# 02cpu_power.net
KiCad netlist of a schematic drawn in Altium Designer
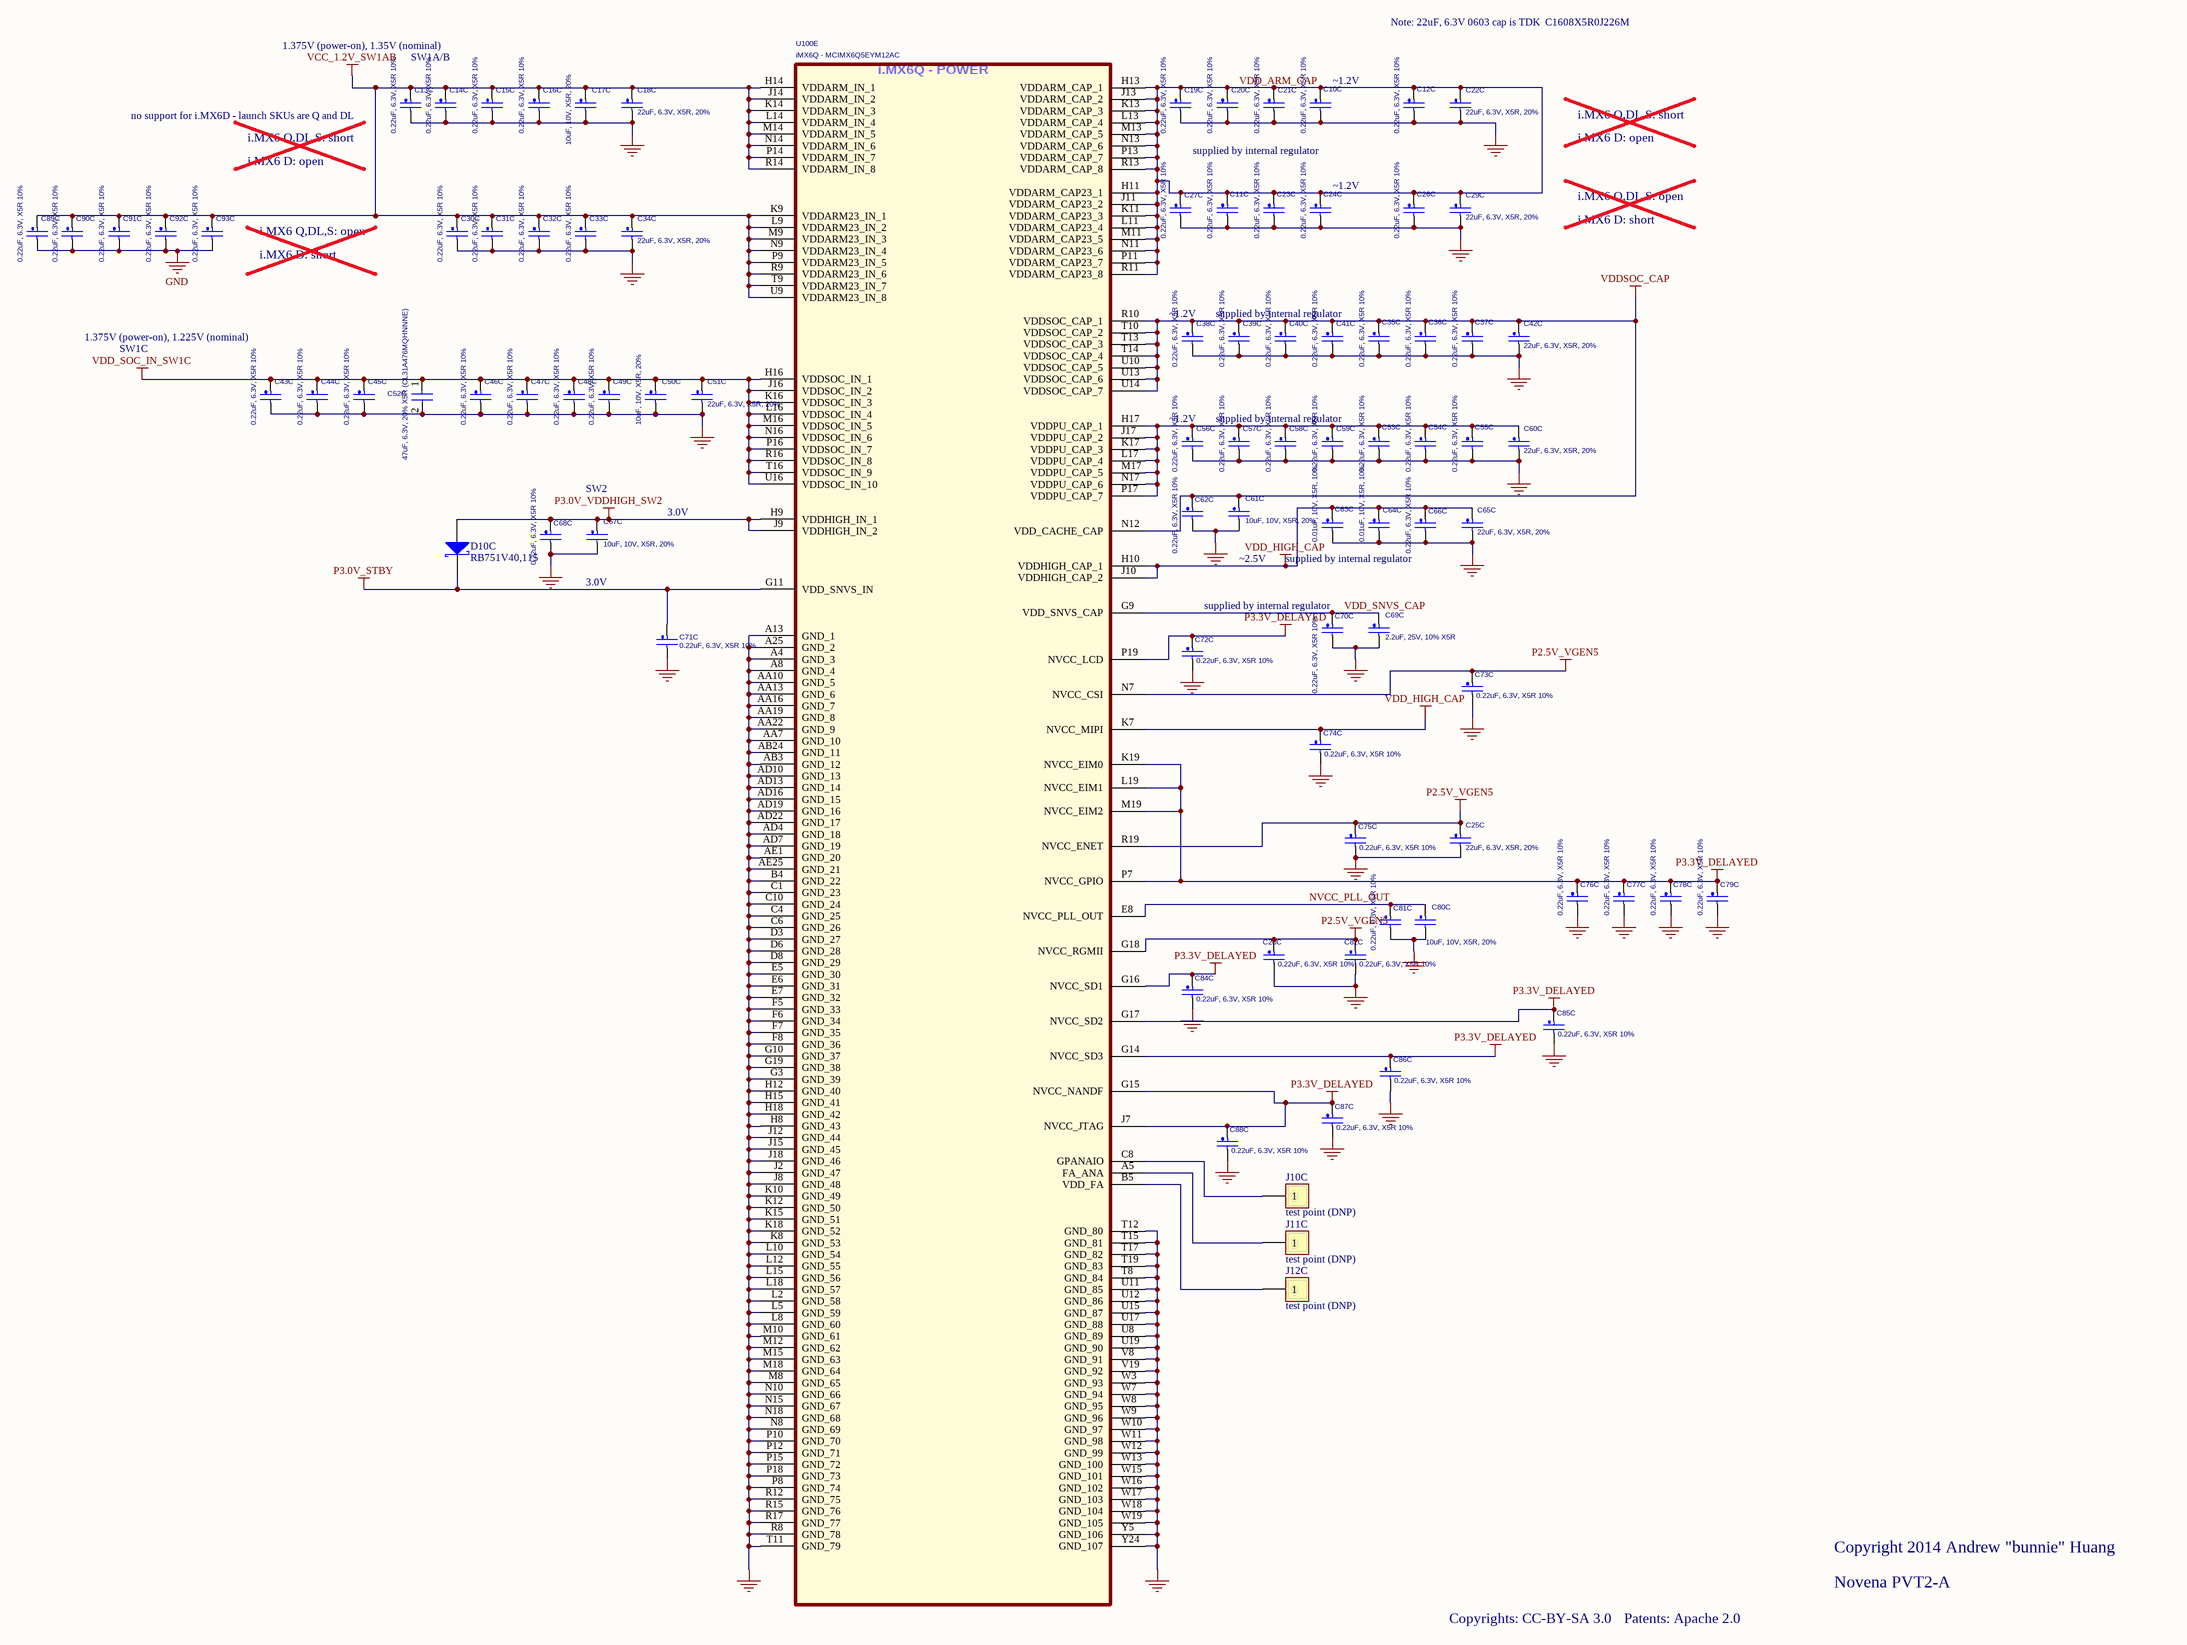
[diagram p0: 02cpu_power.SchDoc]

(export (version "E")
  (design (tool "Eeschema 10.0.6"))
  (components
    (comp (ref "C10C")
      (value "0.22uF, 6.3V, X5R 10%")
      (footprint "CAPC0603N_B")
      (description "CAP CER 0.22UF 6.3V 20% X5R 0201")
      (fields (field (name "TOLERANCE") "10%"))
      (libsource (lib "*") (part "CAP_NP_Dup1"))
    )
    (comp (ref "C11C")
      (value "0.22uF, 6.3V, X5R 10%")
      (footprint "CAPC0603N_B")
      (description "CAP CER 0.22UF 6.3V 20% X5R 0201")
      (fields (field (name "TOLERANCE") "10%"))
      (libsource (lib "*") (part "CAP_NP_Dup1"))
    )
    (comp (ref "C12C")
      (value "0.22uF, 6.3V, X5R 10%")
      (footprint "CAPC0603N_B")
      (description "CAP CER 0.22UF 6.3V 20% X5R 0201")
      (fields (field (name "TOLERANCE") "10%"))
      (libsource (lib "*") (part "CAP_NP_Dup1"))
    )
    (comp (ref "C13C")
      (value "0.22uF, 6.3V, X5R 10%")
      (footprint "CAPC0603N_B")
      (description "CAP CER 0.22UF 6.3V 20% X5R 0201")
      (fields (field (name "TOLERANCE") "20%"))
      (libsource (lib "*") (part "CAP_NP_Dup1"))
    )
    (comp (ref "C14C")
      (value "0.22uF, 6.3V, X5R 10%")
      (footprint "CAPC0603N_B")
      (description "CAP CER 0.22UF 6.3V 20% X5R 0201")
      (fields (field (name "TOLERANCE") "20%"))
      (libsource (lib "*") (part "CAP_NP_Dup1"))
    )
    (comp (ref "C15C")
      (value "0.22uF, 6.3V, X5R 10%")
      (footprint "CAPC0603N_B")
      (description "CAP CER 0.22UF 6.3V 20% X5R 0201")
      (fields (field (name "TOLERANCE") "20%"))
      (libsource (lib "*") (part "CAP_NP_Dup1"))
    )
    (comp (ref "C16C")
      (value "0.22uF, 6.3V, X5R 10%")
      (footprint "CAPC0603N_B")
      (description "CAP CER 0.22UF 6.3V 20% X5R 0201")
      (fields (field (name "TOLERANCE") "20%"))
      (libsource (lib "*") (part "CAP_NP_Dup1"))
    )
    (comp (ref "C17C")
      (value "10uF, 10V, X5R, 20%")
      (footprint "CAPC1608N_HD")
      (description "CAP CER 10UF 6.3V 10% X5R 0603")
      (fields (field (name "TOLERANCE") "10%"))
      (libsource (lib "*") (part "CAP_NP_Dup1"))
    )
    (comp (ref "C18C")
      (value "22uF, 6.3V, X5R, 20%")
      (footprint "CAPC1608N_HD")
      (description "22uF, 10V, X5R, 20%")
      (fields (field (name "TOLERANCE") "20%"))
      (libsource (lib "*") (part "CAP_NP_Dup1"))
    )
    (comp (ref "C19C")
      (value "0.22uF, 6.3V, X5R 10%")
      (footprint "CAPC0603N_B")
      (description "CAP CER 0.22UF 6.3V 20% X5R 0201")
      (fields (field (name "TOLERANCE") "20%"))
      (libsource (lib "*") (part "CAP_NP_Dup1"))
    )
    (comp (ref "C20C")
      (value "0.22uF, 6.3V, X5R 10%")
      (footprint "CAPC0603N_B")
      (description "CAP CER 0.22UF 6.3V 20% X5R 0201")
      (fields (field (name "TOLERANCE") "20%"))
      (libsource (lib "*") (part "CAP_NP_Dup1"))
    )
    (comp (ref "C21C")
      (value "0.22uF, 6.3V, X5R 10%")
      (footprint "CAPC0603N_B")
      (description "CAP CER 0.22UF 6.3V 20% X5R 0201")
      (fields (field (name "TOLERANCE") "20%"))
      (libsource (lib "*") (part "CAP_NP_Dup1"))
    )
    (comp (ref "C22C")
      (value "22uF, 6.3V, X5R, 20%")
      (footprint "CAPC1608N_HD")
      (description "22uF, 10V, X5R, 20%")
      (fields (field (name "TOLERANCE") "20%"))
      (libsource (lib "*") (part "CAP_NP_Dup1"))
    )
    (comp (ref "C23C")
      (value "0.22uF, 6.3V, X5R 10%")
      (footprint "CAPC0603N_B")
      (description "CAP CER 0.22UF 6.3V 20% X5R 0201")
      (fields (field (name "TOLERANCE") "20%"))
      (libsource (lib "*") (part "CAP_NP_Dup1"))
    )
    (comp (ref "C24C")
      (value "0.22uF, 6.3V, X5R 10%")
      (footprint "CAPC0603N_B")
      (description "CAP CER 0.22UF 6.3V 20% X5R 0201")
      (fields (field (name "TOLERANCE") "10%"))
      (libsource (lib "*") (part "CAP_NP_Dup1"))
    )
    (comp (ref "C25C")
      (value "22uF, 6.3V, X5R, 20%")
      (footprint "CAPC1608N_HD")
      (description "22uF, 10V, X5R, 20%")
      (fields (field (name "TOLERANCE") "20%"))
      (libsource (lib "*") (part "CAP_NP_Dup1"))
    )
    (comp (ref "C26C")
      (value "0.22uF, 6.3V, X5R 10%")
      (footprint "CAPC0603N_B")
      (description "CAP CER 0.22UF 6.3V 20% X5R 0201")
      (fields (field (name "TOLERANCE") "10%"))
      (libsource (lib "*") (part "CAP_NP_Dup1"))
    )
    (comp (ref "C27C")
      (value "0.22uF, 6.3V, X5R 10%")
      (footprint "CAPC0603N_B")
      (description "CAP CER 0.22UF 6.3V 20% X5R 0201")
      (fields (field (name "TOLERANCE") "20%"))
      (libsource (lib "*") (part "CAP_NP_Dup1"))
    )
    (comp (ref "C28C")
      (value "0.22uF, 6.3V, X5R 10%")
      (footprint "CAPC0603N_B")
      (description "CAP CER 0.22UF 6.3V 20% X5R 0201")
      (fields (field (name "TOLERANCE") "20%"))
      (libsource (lib "*") (part "CAP_NP_Dup1"))
    )
    (comp (ref "C29C")
      (value "22uF, 6.3V, X5R, 20%")
      (footprint "CAPC1608N_HD")
      (description "22uF, 10V, X5R, 20%")
      (fields (field (name "TOLERANCE") "20%"))
      (libsource (lib "*") (part "CAP_NP_Dup1"))
    )
    (comp (ref "C30C")
      (value "0.22uF, 6.3V, X5R 10%")
      (footprint "CAPC0603N_B")
      (description "CAP CER 0.22UF 6.3V 20% X5R 0201")
      (fields (field (name "TOLERANCE") "20%"))
      (libsource (lib "*") (part "CAP_NP_Dup1"))
    )
    (comp (ref "C31C")
      (value "0.22uF, 6.3V, X5R 10%")
      (footprint "CAPC0603N_B")
      (description "CAP CER 0.22UF 6.3V 20% X5R 0201")
      (fields (field (name "TOLERANCE") "20%"))
      (libsource (lib "*") (part "CAP_NP_Dup1"))
    )
    (comp (ref "C32C")
      (value "0.22uF, 6.3V, X5R 10%")
      (footprint "CAPC0603N_B")
      (description "CAP CER 0.22UF 6.3V 20% X5R 0201")
      (fields (field (name "TOLERANCE") "20%"))
      (libsource (lib "*") (part "CAP_NP_Dup1"))
    )
    (comp (ref "C33C")
      (value "0.22uF, 6.3V, X5R 10%")
      (footprint "CAPC0603N_B")
      (description "CAP CER 0.22UF 6.3V 20% X5R 0201")
      (fields (field (name "TOLERANCE") "20%"))
      (libsource (lib "*") (part "CAP_NP_Dup1"))
    )
    (comp (ref "C34C")
      (value "22uF, 6.3V, X5R, 20%")
      (footprint "CAPC1608N_HD")
      (description "22uF, 10V, X5R, 20%")
      (fields (field (name "TOLERANCE") "20%"))
      (libsource (lib "*") (part "CAP_NP_Dup1"))
    )
    (comp (ref "C35C")
      (value "0.22uF, 6.3V, X5R 10%")
      (footprint "CAPC0603N_B")
      (description "CAP CER 0.22UF 6.3V 20% X5R 0201")
      (fields (field (name "TOLERANCE") "10%"))
      (libsource (lib "*") (part "CAP_NP_Dup1"))
    )
    (comp (ref "C36C")
      (value "0.22uF, 6.3V, X5R 10%")
      (footprint "CAPC0603N_B")
      (description "CAP CER 0.22UF 6.3V 20% X5R 0201")
      (fields (field (name "TOLERANCE") "10%"))
      (libsource (lib "*") (part "CAP_NP_Dup1"))
    )
    (comp (ref "C37C")
      (value "0.22uF, 6.3V, X5R 10%")
      (footprint "CAPC0603N_B")
      (description "CAP CER 0.22UF 6.3V 20% X5R 0201")
      (fields (field (name "TOLERANCE") "10%"))
      (libsource (lib "*") (part "CAP_NP_Dup1"))
    )
    (comp (ref "C38C")
      (value "0.22uF, 6.3V, X5R 10%")
      (footprint "CAPC0603N_B")
      (description "CAP CER 0.22UF 6.3V 20% X5R 0201")
      (fields (field (name "TOLERANCE") "20%"))
      (libsource (lib "*") (part "CAP_NP_Dup1"))
    )
    (comp (ref "C39C")
      (value "0.22uF, 6.3V, X5R 10%")
      (footprint "CAPC0603N_B")
      (description "CAP CER 0.22UF 6.3V 20% X5R 0201")
      (fields (field (name "TOLERANCE") "20%"))
      (libsource (lib "*") (part "CAP_NP_Dup1"))
    )
    (comp (ref "C40C")
      (value "0.22uF, 6.3V, X5R 10%")
      (footprint "CAPC0603N_B")
      (description "CAP CER 0.22UF 6.3V 20% X5R 0201")
      (fields (field (name "TOLERANCE") "20%"))
      (libsource (lib "*") (part "CAP_NP_Dup1"))
    )
    (comp (ref "C41C")
      (value "0.22uF, 6.3V, X5R 10%")
      (footprint "CAPC0603N_B")
      (description "CAP CER 0.22UF 6.3V 20% X5R 0201")
      (fields (field (name "TOLERANCE") "20%"))
      (libsource (lib "*") (part "CAP_NP_Dup1"))
    )
    (comp (ref "C42C")
      (value "22uF, 6.3V, X5R, 20%")
      (footprint "CAPC1608N_HD")
      (description "22uF, 10V, X5R, 20%")
      (fields (field (name "TOLERANCE") "20%"))
      (libsource (lib "*") (part "CAP_NP_Dup1"))
    )
    (comp (ref "C43C")
      (value "0.22uF, 6.3V, X5R 10%")
      (footprint "CAPC0603N_B")
      (description "CAP CER 0.22UF 6.3V 20% X5R 0201")
      (fields (field (name "TOLERANCE") "20%"))
      (libsource (lib "*") (part "CAP_NP_Dup1"))
    )
    (comp (ref "C44C")
      (value "0.22uF, 6.3V, X5R 10%")
      (footprint "CAPC0603N_B")
      (description "CAP CER 0.22UF 6.3V 20% X5R 0201")
      (fields (field (name "TOLERANCE") "20%"))
      (libsource (lib "*") (part "CAP_NP_Dup1"))
    )
    (comp (ref "C45C")
      (value "0.22uF, 6.3V, X5R 10%")
      (footprint "CAPC0603N_B")
      (description "CAP CER 0.22UF 6.3V 20% X5R 0201")
      (fields (field (name "TOLERANCE") "20%"))
      (libsource (lib "*") (part "CAP_NP_Dup1"))
    )
    (comp (ref "C46C")
      (value "0.22uF, 6.3V, X5R 10%")
      (footprint "CAPC0603N_B")
      (description "CAP CER 0.22UF 6.3V 20% X5R 0201")
      (fields (field (name "TOLERANCE") "20%"))
      (libsource (lib "*") (part "CAP_NP_Dup1"))
    )
    (comp (ref "C47C")
      (value "0.22uF, 6.3V, X5R 10%")
      (footprint "CAPC0603N_B")
      (description "CAP CER 0.22UF 6.3V 20% X5R 0201")
      (fields (field (name "TOLERANCE") "20%"))
      (libsource (lib "*") (part "CAP_NP_Dup1"))
    )
    (comp (ref "C48C")
      (value "0.22uF, 6.3V, X5R 10%")
      (footprint "CAPC0603N_B")
      (description "CAP CER 0.22UF 6.3V 20% X5R 0201")
      (fields (field (name "TOLERANCE") "20%"))
      (libsource (lib "*") (part "CAP_NP_Dup1"))
    )
    (comp (ref "C49C")
      (value "0.22uF, 6.3V, X5R 10%")
      (footprint "CAPC0603N_B")
      (description "CAP CER 0.22UF 6.3V 20% X5R 0201")
      (fields (field (name "TOLERANCE") "20%"))
      (libsource (lib "*") (part "CAP_NP_Dup1"))
    )
    (comp (ref "C50C")
      (value "10uF, 10V, X5R, 20%")
      (footprint "CAPC1608N_HD")
      (description "CAP CER 10UF 6.3V 10% X5R 0603")
      (fields (field (name "TOLERANCE") "10%"))
      (libsource (lib "*") (part "CAP_NP_Dup1"))
    )
    (comp (ref "C51C")
      (value "22uF, 6.3V, X5R, 20%")
      (footprint "CAPC1608N_HD")
      (description "22uF, 10V, X5R, 20%")
      (fields (field (name "TOLERANCE") "20%"))
      (libsource (lib "*") (part "CAP_NP_Dup1"))
    )
    (comp (ref "C52C")
      (value "47uF, 6.3V, 20% X5R (CL31A476MQHNNNE)")
      (footprint "CAPC3216N")
      (libsource (lib "*") (part "C"))
    )
    (comp (ref "C53C")
      (value "0.22uF, 6.3V, X5R 10%")
      (footprint "CAPC0603N_B")
      (description "CAP CER 0.22UF 6.3V 20% X5R 0201")
      (fields (field (name "TOLERANCE") "10%"))
      (libsource (lib "*") (part "CAP_NP_Dup1"))
    )
    (comp (ref "C54C")
      (value "0.22uF, 6.3V, X5R 10%")
      (footprint "CAPC0603N_B")
      (description "CAP CER 0.22UF 6.3V 20% X5R 0201")
      (fields (field (name "TOLERANCE") "10%"))
      (libsource (lib "*") (part "CAP_NP_Dup1"))
    )
    (comp (ref "C55C")
      (value "0.22uF, 6.3V, X5R 10%")
      (footprint "CAPC0603N_B")
      (description "CAP CER 0.22UF 6.3V 20% X5R 0201")
      (fields (field (name "TOLERANCE") "10%"))
      (libsource (lib "*") (part "CAP_NP_Dup1"))
    )
    (comp (ref "C56C")
      (value "0.22uF, 6.3V, X5R 10%")
      (footprint "CAPC0603N_B")
      (description "CAP CER 0.22UF 6.3V 20% X5R 0201")
      (fields (field (name "TOLERANCE") "20%"))
      (libsource (lib "*") (part "CAP_NP_Dup1"))
    )
    (comp (ref "C57C")
      (value "0.22uF, 6.3V, X5R 10%")
      (footprint "CAPC0603N_B")
      (description "CAP CER 0.22UF 6.3V 20% X5R 0201")
      (fields (field (name "TOLERANCE") "20%"))
      (libsource (lib "*") (part "CAP_NP_Dup1"))
    )
    (comp (ref "C58C")
      (value "0.22uF, 6.3V, X5R 10%")
      (footprint "CAPC0603N_B")
      (description "CAP CER 0.22UF 6.3V 20% X5R 0201")
      (fields (field (name "TOLERANCE") "20%"))
      (libsource (lib "*") (part "CAP_NP_Dup1"))
    )
    (comp (ref "C59C")
      (value "0.22uF, 6.3V, X5R 10%")
      (footprint "CAPC0603N_B")
      (description "CAP CER 0.22UF 6.3V 20% X5R 0201")
      (fields (field (name "TOLERANCE") "20%"))
      (libsource (lib "*") (part "CAP_NP_Dup1"))
    )
    (comp (ref "C60C")
      (value "22uF, 6.3V, X5R, 20%")
      (footprint "CAPC1608N_HD")
      (description "22uF, 10V, X5R, 20%")
      (fields (field (name "TOLERANCE") "20%"))
      (libsource (lib "*") (part "CAP_NP_Dup1"))
    )
    (comp (ref "C61C")
      (value "10uF, 10V, X5R, 20%")
      (footprint "CAPC1608N_HD")
      (description "CAP CER 10UF 6.3V 10% X5R 0603")
      (fields (field (name "TOLERANCE") "10%"))
      (libsource (lib "*") (part "CAP_NP_Dup1"))
    )
    (comp (ref "C62C")
      (value "0.22uF, 6.3V, X5R 10%")
      (footprint "CAPC0603N_B")
      (description "CAP CER 0.22UF 6.3V 20% X5R 0201")
      (fields (field (name "TOLERANCE") "20%"))
      (libsource (lib "*") (part "CAP_NP_Dup1"))
    )
    (comp (ref "C63C")
      (value "0.01uF, 10V, X5R, 10%")
      (footprint "CAPC0603N_B")
      (description "0.01uF, 10V, X5R")
      (fields (field (name "TOLERANCE") "10%"))
      (libsource (lib "*") (part "CAP_NP_Dup1"))
    )
    (comp (ref "C64C")
      (value "0.01uF, 10V, X5R, 10%")
      (footprint "CAPC0603N_B")
      (description "0.01uF, 10V, X5R")
      (fields (field (name "TOLERANCE") "10%"))
      (libsource (lib "*") (part "CAP_NP_Dup1"))
    )
    (comp (ref "C65C")
      (value "22uF, 6.3V, X5R, 20%")
      (footprint "CAPC1608N_HD")
      (description "22uF, 10V, X5R, 20%")
      (fields (field (name "TOLERANCE") "20%"))
      (libsource (lib "*") (part "CAP_NP_Dup1"))
    )
    (comp (ref "C66C")
      (value "0.22uF, 6.3V, X5R 10%")
      (footprint "CAPC0603N_B")
      (description "CAP CER 0.22UF 6.3V 20% X5R 0201")
      (fields (field (name "TOLERANCE") "20%"))
      (libsource (lib "*") (part "CAP_NP_Dup1"))
    )
    (comp (ref "C67C")
      (value "10uF, 10V, X5R, 20%")
      (footprint "CAPC1608N_HD")
      (description "CAP CER 10UF 6.3V 10% X5R 0603")
      (fields (field (name "TOLERANCE") "10%"))
      (libsource (lib "*") (part "CAP_NP_Dup1"))
    )
    (comp (ref "C68C")
      (value "0.22uF, 6.3V, X5R 10%")
      (footprint "CAPC0603N_B")
      (description "CAP CER 0.22UF 6.3V 20% X5R 0201")
      (fields (field (name "TOLERANCE") "20%"))
      (libsource (lib "*") (part "CAP_NP_Dup1"))
    )
    (comp (ref "C69C")
      (value "2.2uF, 25V, 10% X5R")
      (footprint "CAPC1608N_HD")
      (description "CAP CER 2.2UF 25V 10% X5R 0603")
      (fields (field (name "TOLERANCE") "10%"))
      (libsource (lib "*") (part "CAP_NP_Dup1"))
    )
    (comp (ref "C70C")
      (value "0.22uF, 6.3V, X5R 10%")
      (footprint "CAPC0603N_B")
      (description "CAP CER 0.22UF 6.3V 20% X5R 0201")
      (fields (field (name "TOLERANCE") "20%"))
      (libsource (lib "*") (part "CAP_NP_Dup1"))
    )
    (comp (ref "C71C")
      (value "0.22uF, 6.3V, X5R 10%")
      (footprint "CAPC0603N_B")
      (description "CAP CER 0.22UF 6.3V 20% X5R 0201")
      (fields (field (name "TOLERANCE") "20%"))
      (libsource (lib "*") (part "CAP_NP_Dup1"))
    )
    (comp (ref "C72C")
      (value "0.22uF, 6.3V, X5R 10%")
      (footprint "CAPC0603N_B")
      (description "CAP CER 0.22UF 6.3V 20% X5R 0201")
      (fields (field (name "TOLERANCE") "20%"))
      (libsource (lib "*") (part "CAP_NP_Dup1"))
    )
    (comp (ref "C73C")
      (value "0.22uF, 6.3V, X5R 10%")
      (footprint "CAPC0603N_B")
      (description "CAP CER 0.22UF 6.3V 20% X5R 0201")
      (fields (field (name "TOLERANCE") "20%"))
      (libsource (lib "*") (part "CAP_NP_Dup1"))
    )
    (comp (ref "C74C")
      (value "0.22uF, 6.3V, X5R 10%")
      (footprint "CAPC0603N_B")
      (description "CAP CER 0.22UF 6.3V 20% X5R 0201")
      (fields (field (name "TOLERANCE") "20%"))
      (libsource (lib "*") (part "CAP_NP_Dup1"))
    )
    (comp (ref "C75C")
      (value "0.22uF, 6.3V, X5R 10%")
      (footprint "CAPC0603N_B")
      (description "CAP CER 0.22UF 6.3V 20% X5R 0201")
      (fields (field (name "TOLERANCE") "20%"))
      (libsource (lib "*") (part "CAP_NP_Dup1"))
    )
    (comp (ref "C76C")
      (value "0.22uF, 6.3V, X5R 10%")
      (footprint "CAPC0603N_B")
      (description "CAP CER 0.22UF 6.3V 20% X5R 0201")
      (fields (field (name "TOLERANCE") "20%"))
      (libsource (lib "*") (part "CAP_NP_Dup1"))
    )
    (comp (ref "C77C")
      (value "0.22uF, 6.3V, X5R 10%")
      (footprint "CAPC0603N_B")
      (description "CAP CER 0.22UF 6.3V 20% X5R 0201")
      (fields (field (name "TOLERANCE") "20%"))
      (libsource (lib "*") (part "CAP_NP_Dup1"))
    )
    (comp (ref "C78C")
      (value "0.22uF, 6.3V, X5R 10%")
      (footprint "CAPC0603N_B")
      (description "CAP CER 0.22UF 6.3V 20% X5R 0201")
      (fields (field (name "TOLERANCE") "20%"))
      (libsource (lib "*") (part "CAP_NP_Dup1"))
    )
    (comp (ref "C79C")
      (value "0.22uF, 6.3V, X5R 10%")
      (footprint "CAPC0603N_B")
      (description "CAP CER 0.22UF 6.3V 20% X5R 0201")
      (fields (field (name "TOLERANCE") "20%"))
      (libsource (lib "*") (part "CAP_NP_Dup1"))
    )
    (comp (ref "C80C")
      (value "10uF, 10V, X5R, 20%")
      (footprint "CAPC1608N_HD")
      (description "CAP CER 10UF 6.3V 10% X5R 0603")
      (fields (field (name "TOLERANCE") "10%"))
      (libsource (lib "*") (part "CAP_NP_Dup1"))
    )
    (comp (ref "C81C")
      (value "0.22uF, 6.3V, X5R 10%")
      (footprint "CAPC0603N_B")
      (description "CAP CER 0.22UF 6.3V 20% X5R 0201")
      (fields (field (name "TOLERANCE") "20%"))
      (libsource (lib "*") (part "CAP_NP_Dup1"))
    )
    (comp (ref "C82C")
      (value "0.22uF, 6.3V, X5R 10%")
      (footprint "CAPC0603N_B")
      (description "CAP CER 0.22UF 6.3V 20% X5R 0201")
      (fields (field (name "TOLERANCE") "20%"))
      (libsource (lib "*") (part "CAP_NP_Dup1"))
    )
    (comp (ref "C84C")
      (value "0.22uF, 6.3V, X5R 10%")
      (footprint "CAPC0603N_B")
      (description "CAP CER 0.22UF 6.3V 20% X5R 0201")
      (fields (field (name "TOLERANCE") "20%"))
      (libsource (lib "*") (part "CAP_NP_Dup1"))
    )
    (comp (ref "C85C")
      (value "0.22uF, 6.3V, X5R 10%")
      (footprint "CAPC0603N_B")
      (description "CAP CER 0.22UF 6.3V 20% X5R 0201")
      (fields (field (name "TOLERANCE") "20%"))
      (libsource (lib "*") (part "CAP_NP_Dup1"))
    )
    (comp (ref "C86C")
      (value "0.22uF, 6.3V, X5R 10%")
      (footprint "CAPC0603N_B")
      (description "CAP CER 0.22UF 6.3V 20% X5R 0201")
      (fields (field (name "TOLERANCE") "20%"))
      (libsource (lib "*") (part "CAP_NP_Dup1"))
    )
    (comp (ref "C87C")
      (value "0.22uF, 6.3V, X5R 10%")
      (footprint "CAPC0603N_B")
      (description "CAP CER 0.22UF 6.3V 20% X5R 0201")
      (fields (field (name "TOLERANCE") "20%"))
      (libsource (lib "*") (part "CAP_NP_Dup1"))
    )
    (comp (ref "C88C")
      (value "0.22uF, 6.3V, X5R 10%")
      (footprint "CAPC0603N_B")
      (description "CAP CER 0.22UF 6.3V 20% X5R 0201")
      (fields (field (name "TOLERANCE") "20%"))
      (libsource (lib "*") (part "CAP_NP_Dup1"))
    )
    (comp (ref "C89C")
      (value "0.22uF, 6.3V, X5R 10%")
      (footprint "CAPC0603N_B")
      (description "CAP CER 0.22UF 6.3V 20% X5R 0201")
      (fields (field (name "TOLERANCE") "20%"))
      (libsource (lib "*") (part "CAP_NP_Dup1"))
    )
    (comp (ref "C90C")
      (value "0.22uF, 6.3V, X5R 10%")
      (footprint "CAPC0603N_B")
      (description "CAP CER 0.22UF 6.3V 20% X5R 0201")
      (fields (field (name "TOLERANCE") "20%"))
      (libsource (lib "*") (part "CAP_NP_Dup1"))
    )
    (comp (ref "C91C")
      (value "0.22uF, 6.3V, X5R 10%")
      (footprint "CAPC0603N_B")
      (description "CAP CER 0.22UF 6.3V 20% X5R 0201")
      (fields (field (name "TOLERANCE") "20%"))
      (libsource (lib "*") (part "CAP_NP_Dup1"))
    )
    (comp (ref "C92C")
      (value "0.22uF, 6.3V, X5R 10%")
      (footprint "CAPC0603N_B")
      (description "CAP CER 0.22UF 6.3V 20% X5R 0201")
      (fields (field (name "TOLERANCE") "20%"))
      (libsource (lib "*") (part "CAP_NP_Dup1"))
    )
    (comp (ref "C93C")
      (value "0.22uF, 6.3V, X5R 10%")
      (footprint "CAPC0603N_B")
      (description "CAP CER 0.22UF 6.3V 20% X5R 0201")
      (fields (field (name "TOLERANCE") "20%"))
      (libsource (lib "*") (part "CAP_NP_Dup1"))
    )
    (comp (ref "D10C")
      (value "RB751V40,115")
      (footprint "SOD-323")
      (description "Schottky Diode")
      (fields (field (name "PUBLISHER") "Altium Limited"))
      (libsource (lib "Miscellaneous Devices") (part "D Schottky"))
    )
    (comp (ref "J10C")
      (value "test point (DNP)")
      (footprint "TP_SMT_38mil")
      (description "Connector")
      (libsource (lib "*") (part "CON1"))
    )
    (comp (ref "J11C")
      (value "test point (DNP)")
      (footprint "TP_SMT_38mil")
      (description "Connector")
      (libsource (lib "*") (part "CON1"))
    )
    (comp (ref "J12C")
      (value "test point (DNP)")
      (footprint "TP_SMT_38mil")
      (description "Connector")
      (libsource (lib "*") (part "CON1"))
    )
    (comp (ref "U100")
      (value "iMX6Q - MCIMX6Q5EYM12AC")
      (description "PCIMX6Q5EVT10AC")
      (libsource (lib "*") (part "PCIMX6Q6VV1A"))
    )
  )
  (nets
    (net (code "1") (name "/NVCC_PLL_OUT") (class "Default")
      (node (ref "C80C") (pin "1") (pinfunction "1_1") (pintype "passive"))
      (node (ref "C81C") (pin "1") (pinfunction "1_1") (pintype "passive"))
      (node (ref "U100") (pin "E8") (pinfunction "NVCC_PLL_OUT_E8") (pintype "power_in"))
    )
    (net (code "2") (name "/VDD_ARM_CAP") (class "Default")
      (node (ref "C10C") (pin "1") (pinfunction "1_1") (pintype "passive"))
      (node (ref "C11C") (pin "1") (pinfunction "1_1") (pintype "passive"))
      (node (ref "C12C") (pin "1") (pinfunction "1_1") (pintype "passive"))
      (node (ref "C19C") (pin "1") (pinfunction "1_1") (pintype "passive"))
      (node (ref "C20C") (pin "1") (pinfunction "1_1") (pintype "passive"))
      (node (ref "C21C") (pin "1") (pinfunction "1_1") (pintype "passive"))
      (node (ref "C22C") (pin "1") (pinfunction "1_1") (pintype "passive"))
      (node (ref "C23C") (pin "1") (pinfunction "1_1") (pintype "passive"))
      (node (ref "C24C") (pin "1") (pinfunction "1_1") (pintype "passive"))
      (node (ref "C26C") (pin "1") (pinfunction "1_1") (pintype "passive"))
      (node (ref "C27C") (pin "1") (pinfunction "1_1") (pintype "passive"))
      (node (ref "C29C") (pin "1") (pinfunction "1_1") (pintype "passive"))
      (node (ref "U100") (pin "H11") (pinfunction "VDDARM_CAP23_1_H11") (pintype "power_in"))
      (node (ref "U100") (pin "H13") (pinfunction "VDDARM_CAP_1_H13") (pintype "power_in"))
      (node (ref "U100") (pin "J11") (pinfunction "VDDARM_CAP23_2_J11") (pintype "power_in"))
      (node (ref "U100") (pin "J13") (pinfunction "VDDARM_CAP_2_J13") (pintype "power_in"))
      (node (ref "U100") (pin "K11") (pinfunction "VDDARM_CAP23_3_K11") (pintype "power_in"))
      (node (ref "U100") (pin "K13") (pinfunction "VDDARM_CAP_3_K13") (pintype "power_in"))
      (node (ref "U100") (pin "L11") (pinfunction "VDDARM_CAP23_4_L11") (pintype "power_in"))
      (node (ref "U100") (pin "L13") (pinfunction "VDDARM_CAP_4_L13") (pintype "power_in"))
      (node (ref "U100") (pin "M11") (pinfunction "VDDARM_CAP23_5_M11") (pintype "power_in"))
      (node (ref "U100") (pin "M13") (pinfunction "VDDARM_CAP_5_M13") (pintype "power_in"))
      (node (ref "U100") (pin "N11") (pinfunction "VDDARM_CAP23_6_N11") (pintype "power_in"))
      (node (ref "U100") (pin "N13") (pinfunction "VDDARM_CAP_6_N13") (pintype "power_in"))
      (node (ref "U100") (pin "P11") (pinfunction "VDDARM_CAP23_7_P11") (pintype "power_in"))
      (node (ref "U100") (pin "P13") (pinfunction "VDDARM_CAP_7_P13") (pintype "power_in"))
      (node (ref "U100") (pin "R11") (pinfunction "VDDARM_CAP23_8_R11") (pintype "power_in"))
      (node (ref "U100") (pin "R13") (pinfunction "VDDARM_CAP_8_R13") (pintype "power_in"))
    )
    (net (code "3") (name "/VDD_SNVS_CAP") (class "Default")
      (node (ref "C69C") (pin "1") (pinfunction "1_1") (pintype "passive"))
      (node (ref "C70C") (pin "1") (pinfunction "1_1") (pintype "passive"))
      (node (ref "U100") (pin "G9") (pinfunction "VDD_SNVS_CAP_G9") (pintype "power_in"))
    )
    (net (code "4") (name "GND") (class "Default")
      (node (ref "C10C") (pin "2") (pinfunction "2_2") (pintype "passive"))
      (node (ref "C11C") (pin "2") (pinfunction "2_2") (pintype "passive"))
      (node (ref "C12C") (pin "2") (pinfunction "2_2") (pintype "passive"))
      (node (ref "C13C") (pin "2") (pinfunction "2_2") (pintype "passive"))
      (node (ref "C14C") (pin "2") (pinfunction "2_2") (pintype "passive"))
      (node (ref "C15C") (pin "2") (pinfunction "2_2") (pintype "passive"))
      (node (ref "C16C") (pin "2") (pinfunction "2_2") (pintype "passive"))
      (node (ref "C17C") (pin "2") (pinfunction "2_2") (pintype "passive"))
      (node (ref "C18C") (pin "2") (pinfunction "2_2") (pintype "passive"))
      (node (ref "C19C") (pin "2") (pinfunction "2_2") (pintype "passive"))
      (node (ref "C20C") (pin "2") (pinfunction "2_2") (pintype "passive"))
      (node (ref "C21C") (pin "2") (pinfunction "2_2") (pintype "passive"))
      (node (ref "C22C") (pin "2") (pinfunction "2_2") (pintype "passive"))
      (node (ref "C23C") (pin "2") (pinfunction "2_2") (pintype "passive"))
      (node (ref "C24C") (pin "2") (pinfunction "2_2") (pintype "passive"))
      (node (ref "C25C") (pin "2") (pinfunction "2_2") (pintype "passive"))
      (node (ref "C26C") (pin "2") (pinfunction "2_2") (pintype "passive"))
      (node (ref "C27C") (pin "2") (pinfunction "2_2") (pintype "passive"))
      (node (ref "C28C") (pin "2") (pinfunction "2_2") (pintype "passive"))
      (node (ref "C29C") (pin "2") (pinfunction "2_2") (pintype "passive"))
      (node (ref "C30C") (pin "2") (pinfunction "2_2") (pintype "passive"))
      (node (ref "C31C") (pin "2") (pinfunction "2_2") (pintype "passive"))
      (node (ref "C32C") (pin "2") (pinfunction "2_2") (pintype "passive"))
      (node (ref "C33C") (pin "2") (pinfunction "2_2") (pintype "passive"))
      (node (ref "C34C") (pin "2") (pinfunction "2_2") (pintype "passive"))
      (node (ref "C35C") (pin "2") (pinfunction "2_2") (pintype "passive"))
      (node (ref "C36C") (pin "2") (pinfunction "2_2") (pintype "passive"))
      (node (ref "C37C") (pin "2") (pinfunction "2_2") (pintype "passive"))
      (node (ref "C38C") (pin "2") (pinfunction "2_2") (pintype "passive"))
      (node (ref "C39C") (pin "2") (pinfunction "2_2") (pintype "passive"))
      (node (ref "C40C") (pin "2") (pinfunction "2_2") (pintype "passive"))
      (node (ref "C41C") (pin "2") (pinfunction "2_2") (pintype "passive"))
      (node (ref "C42C") (pin "2") (pinfunction "2_2") (pintype "passive"))
      (node (ref "C43C") (pin "2") (pinfunction "2_2") (pintype "passive"))
      (node (ref "C44C") (pin "2") (pinfunction "2_2") (pintype "passive"))
      (node (ref "C45C") (pin "2") (pinfunction "2_2") (pintype "passive"))
      (node (ref "C46C") (pin "2") (pinfunction "2_2") (pintype "passive"))
      (node (ref "C47C") (pin "2") (pinfunction "2_2") (pintype "passive"))
      (node (ref "C48C") (pin "2") (pinfunction "2_2") (pintype "passive"))
      (node (ref "C49C") (pin "2") (pinfunction "2_2") (pintype "passive"))
      (node (ref "C50C") (pin "2") (pinfunction "2_2") (pintype "passive"))
      (node (ref "C51C") (pin "2") (pinfunction "2_2") (pintype "passive"))
      (node (ref "C52C") (pin "2") (pinfunction "2_2") (pintype "passive"))
      (node (ref "C53C") (pin "2") (pinfunction "2_2") (pintype "passive"))
      (node (ref "C54C") (pin "2") (pinfunction "2_2") (pintype "passive"))
      (node (ref "C55C") (pin "2") (pinfunction "2_2") (pintype "passive"))
      (node (ref "C56C") (pin "2") (pinfunction "2_2") (pintype "passive"))
      (node (ref "C57C") (pin "2") (pinfunction "2_2") (pintype "passive"))
      (node (ref "C58C") (pin "2") (pinfunction "2_2") (pintype "passive"))
      (node (ref "C59C") (pin "2") (pinfunction "2_2") (pintype "passive"))
      (node (ref "C60C") (pin "2") (pinfunction "2_2") (pintype "passive"))
      (node (ref "C61C") (pin "2") (pinfunction "2_2") (pintype "passive"))
      (node (ref "C62C") (pin "2") (pinfunction "2_2") (pintype "passive"))
      (node (ref "C63C") (pin "2") (pinfunction "2_2") (pintype "passive"))
      (node (ref "C64C") (pin "2") (pinfunction "2_2") (pintype "passive"))
      (node (ref "C65C") (pin "2") (pinfunction "2_2") (pintype "passive"))
      (node (ref "C66C") (pin "2") (pinfunction "2_2") (pintype "passive"))
      (node (ref "C67C") (pin "2") (pinfunction "2_2") (pintype "passive"))
      (node (ref "C68C") (pin "2") (pinfunction "2_2") (pintype "passive"))
      (node (ref "C69C") (pin "2") (pinfunction "2_2") (pintype "passive"))
      (node (ref "C70C") (pin "2") (pinfunction "2_2") (pintype "passive"))
      (node (ref "C71C") (pin "2") (pinfunction "2_2") (pintype "passive"))
      (node (ref "C72C") (pin "2") (pinfunction "2_2") (pintype "passive"))
      (node (ref "C73C") (pin "2") (pinfunction "2_2") (pintype "passive"))
      (node (ref "C74C") (pin "2") (pinfunction "2_2") (pintype "passive"))
      (node (ref "C75C") (pin "2") (pinfunction "2_2") (pintype "passive"))
      (node (ref "C76C") (pin "2") (pinfunction "2_2") (pintype "passive"))
      (node (ref "C77C") (pin "2") (pinfunction "2_2") (pintype "passive"))
      (node (ref "C78C") (pin "2") (pinfunction "2_2") (pintype "passive"))
      (node (ref "C79C") (pin "2") (pinfunction "2_2") (pintype "passive"))
      (node (ref "C80C") (pin "2") (pinfunction "2_2") (pintype "passive"))
      (node (ref "C81C") (pin "2") (pinfunction "2_2") (pintype "passive"))
      (node (ref "C82C") (pin "2") (pinfunction "2_2") (pintype "passive"))
      (node (ref "C84C") (pin "2") (pinfunction "2_2") (pintype "passive"))
      (node (ref "C85C") (pin "2") (pinfunction "2_2") (pintype "passive"))
      (node (ref "C86C") (pin "2") (pinfunction "2_2") (pintype "passive"))
      (node (ref "C87C") (pin "2") (pinfunction "2_2") (pintype "passive"))
      (node (ref "C88C") (pin "2") (pinfunction "2_2") (pintype "passive"))
      (node (ref "C89C") (pin "2") (pinfunction "2_2") (pintype "passive"))
      (node (ref "C90C") (pin "2") (pinfunction "2_2") (pintype "passive"))
      (node (ref "C91C") (pin "2") (pinfunction "2_2") (pintype "passive"))
      (node (ref "C92C") (pin "2") (pinfunction "2_2") (pintype "passive"))
      (node (ref "C93C") (pin "2") (pinfunction "2_2") (pintype "passive"))
      (node (ref "U100") (pin "A13") (pinfunction "GND_1_A13") (pintype "power_in"))
      (node (ref "U100") (pin "A25") (pinfunction "GND_2_A25") (pintype "power_in"))
      (node (ref "U100") (pin "A4") (pinfunction "GND_3_A4") (pintype "power_in"))
      (node (ref "U100") (pin "A8") (pinfunction "GND_4_A8") (pintype "power_in"))
      (node (ref "U100") (pin "AA10") (pinfunction "GND_5_AA10") (pintype "power_in"))
      (node (ref "U100") (pin "AA13") (pinfunction "GND_6_AA13") (pintype "power_in"))
      (node (ref "U100") (pin "AA16") (pinfunction "GND_7_AA16") (pintype "power_in"))
      (node (ref "U100") (pin "AA19") (pinfunction "GND_8_AA19") (pintype "power_in"))
      (node (ref "U100") (pin "AA22") (pinfunction "GND_9_AA22") (pintype "power_in"))
      (node (ref "U100") (pin "AA7") (pinfunction "GND_10_AA7") (pintype "power_in"))
      (node (ref "U100") (pin "AB24") (pinfunction "GND_11_AB24") (pintype "power_in"))
      (node (ref "U100") (pin "AB3") (pinfunction "GND_12_AB3") (pintype "power_in"))
      (node (ref "U100") (pin "AD10") (pinfunction "GND_13_AD10") (pintype "power_in"))
      (node (ref "U100") (pin "AD13") (pinfunction "GND_14_AD13") (pintype "power_in"))
      (node (ref "U100") (pin "AD16") (pinfunction "GND_15_AD16") (pintype "power_in"))
      (node (ref "U100") (pin "AD19") (pinfunction "GND_16_AD19") (pintype "power_in"))
      (node (ref "U100") (pin "AD22") (pinfunction "GND_17_AD22") (pintype "power_in"))
      (node (ref "U100") (pin "AD4") (pinfunction "GND_18_AD4") (pintype "power_in"))
      (node (ref "U100") (pin "AD7") (pinfunction "GND_19_AD7") (pintype "power_in"))
      (node (ref "U100") (pin "AE1") (pinfunction "GND_20_AE1") (pintype "power_in"))
      (node (ref "U100") (pin "AE25") (pinfunction "GND_21_AE25") (pintype "power_in"))
      (node (ref "U100") (pin "B4") (pinfunction "GND_22_B4") (pintype "power_in"))
      (node (ref "U100") (pin "C1") (pinfunction "GND_23_C1") (pintype "power_in"))
      (node (ref "U100") (pin "C10") (pinfunction "GND_24_C10") (pintype "power_in"))
      (node (ref "U100") (pin "C4") (pinfunction "GND_25_C4") (pintype "power_in"))
      (node (ref "U100") (pin "C6") (pinfunction "GND_26_C6") (pintype "power_in"))
      (node (ref "U100") (pin "D3") (pinfunction "GND_27_D3") (pintype "power_in"))
      (node (ref "U100") (pin "D6") (pinfunction "GND_28_D6") (pintype "power_in"))
      (node (ref "U100") (pin "D8") (pinfunction "GND_29_D8") (pintype "power_in"))
      (node (ref "U100") (pin "E5") (pinfunction "GND_30_E5") (pintype "power_in"))
      (node (ref "U100") (pin "E6") (pinfunction "GND_31_E6") (pintype "power_in"))
      (node (ref "U100") (pin "E7") (pinfunction "GND_32_E7") (pintype "power_in"))
      (node (ref "U100") (pin "F5") (pinfunction "GND_33_F5") (pintype "power_in"))
      (node (ref "U100") (pin "F6") (pinfunction "GND_34_F6") (pintype "power_in"))
      (node (ref "U100") (pin "F7") (pinfunction "GND_35_F7") (pintype "power_in"))
      (node (ref "U100") (pin "F8") (pinfunction "GND_36_F8") (pintype "power_in"))
      (node (ref "U100") (pin "G10") (pinfunction "GND_37_G10") (pintype "power_in"))
      (node (ref "U100") (pin "G19") (pinfunction "GND_38_G19") (pintype "power_in"))
      (node (ref "U100") (pin "G3") (pinfunction "GND_39_G3") (pintype "power_in"))
      (node (ref "U100") (pin "H12") (pinfunction "GND_40_H12") (pintype "power_in"))
      (node (ref "U100") (pin "H15") (pinfunction "GND_41_H15") (pintype "power_in"))
      (node (ref "U100") (pin "H18") (pinfunction "GND_42_H18") (pintype "power_in"))
      (node (ref "U100") (pin "H8") (pinfunction "GND_43_H8") (pintype "power_in"))
      (node (ref "U100") (pin "J12") (pinfunction "GND_44_J12") (pintype "power_in"))
      (node (ref "U100") (pin "J15") (pinfunction "GND_45_J15") (pintype "power_in"))
      (node (ref "U100") (pin "J18") (pinfunction "GND_46_J18") (pintype "power_in"))
      (node (ref "U100") (pin "J2") (pinfunction "GND_47_J2") (pintype "power_in"))
      (node (ref "U100") (pin "J8") (pinfunction "GND_48_J8") (pintype "power_in"))
      (node (ref "U100") (pin "K10") (pinfunction "GND_49_K10") (pintype "power_in"))
      (node (ref "U100") (pin "K12") (pinfunction "GND_50_K12") (pintype "power_in"))
      (node (ref "U100") (pin "K15") (pinfunction "GND_51_K15") (pintype "power_in"))
      (node (ref "U100") (pin "K18") (pinfunction "GND_52_K18") (pintype "power_in"))
      (node (ref "U100") (pin "K8") (pinfunction "GND_53_K8") (pintype "power_in"))
      (node (ref "U100") (pin "L10") (pinfunction "GND_54_L10") (pintype "power_in"))
      (node (ref "U100") (pin "L12") (pinfunction "GND_55_L12") (pintype "power_in"))
      (node (ref "U100") (pin "L15") (pinfunction "GND_56_L15") (pintype "power_in"))
      (node (ref "U100") (pin "L18") (pinfunction "GND_57_L18") (pintype "power_in"))
      (node (ref "U100") (pin "L2") (pinfunction "GND_58_L2") (pintype "power_in"))
      (node (ref "U100") (pin "L5") (pinfunction "GND_59_L5") (pintype "power_in"))
      (node (ref "U100") (pin "L8") (pinfunction "GND_60_L8") (pintype "power_in"))
      (node (ref "U100") (pin "M10") (pinfunction "GND_61_M10") (pintype "power_in"))
      (node (ref "U100") (pin "M12") (pinfunction "GND_62_M12") (pintype "power_in"))
      (node (ref "U100") (pin "M15") (pinfunction "GND_63_M15") (pintype "power_in"))
      (node (ref "U100") (pin "M18") (pinfunction "GND_64_M18") (pintype "power_in"))
      (node (ref "U100") (pin "M8") (pinfunction "GND_65_M8") (pintype "power_in"))
      (node (ref "U100") (pin "N10") (pinfunction "GND_66_N10") (pintype "power_in"))
      (node (ref "U100") (pin "N15") (pinfunction "GND_67_N15") (pintype "power_in"))
      (node (ref "U100") (pin "N18") (pinfunction "GND_68_N18") (pintype "power_in"))
      (node (ref "U100") (pin "N8") (pinfunction "GND_69_N8") (pintype "power_in"))
      (node (ref "U100") (pin "P10") (pinfunction "GND_70_P10") (pintype "power_in"))
      (node (ref "U100") (pin "P12") (pinfunction "GND_71_P12") (pintype "power_in"))
      (node (ref "U100") (pin "P15") (pinfunction "GND_72_P15") (pintype "power_in"))
      (node (ref "U100") (pin "P18") (pinfunction "GND_73_P18") (pintype "power_in"))
      (node (ref "U100") (pin "P8") (pinfunction "GND_74_P8") (pintype "power_in"))
      (node (ref "U100") (pin "R12") (pinfunction "GND_75_R12") (pintype "power_in"))
      (node (ref "U100") (pin "R15") (pinfunction "GND_76_R15") (pintype "power_in"))
      (node (ref "U100") (pin "R17") (pinfunction "GND_77_R17") (pintype "power_in"))
      (node (ref "U100") (pin "R8") (pinfunction "GND_78_R8") (pintype "power_in"))
      (node (ref "U100") (pin "T11") (pinfunction "GND_79_T11") (pintype "power_in"))
      (node (ref "U100") (pin "T12") (pinfunction "GND_80_T12") (pintype "power_in"))
      (node (ref "U100") (pin "T15") (pinfunction "GND_81_T15") (pintype "power_in"))
      (node (ref "U100") (pin "T17") (pinfunction "GND_82_T17") (pintype "power_in"))
      (node (ref "U100") (pin "T19") (pinfunction "GND_83_T19") (pintype "power_in"))
      (node (ref "U100") (pin "T8") (pinfunction "GND_84_T8") (pintype "power_in"))
      (node (ref "U100") (pin "U11") (pinfunction "GND_85_U11") (pintype "power_in"))
      (node (ref "U100") (pin "U12") (pinfunction "GND_86_U12") (pintype "power_in"))
      (node (ref "U100") (pin "U15") (pinfunction "GND_87_U15") (pintype "power_in"))
      (node (ref "U100") (pin "U17") (pinfunction "GND_88_U17") (pintype "power_in"))
      (node (ref "U100") (pin "U19") (pinfunction "GND_90_U19") (pintype "power_in"))
      (node (ref "U100") (pin "U8") (pinfunction "GND_89_U8") (pintype "power_in"))
      (node (ref "U100") (pin "V19") (pinfunction "GND_92_V19") (pintype "power_in"))
      (node (ref "U100") (pin "V8") (pinfunction "GND_91_V8") (pintype "power_in"))
      (node (ref "U100") (pin "W10") (pinfunction "GND_97_W10") (pintype "power_in"))
      (node (ref "U100") (pin "W11") (pinfunction "GND_98_W11") (pintype "power_in"))
      (node (ref "U100") (pin "W12") (pinfunction "GND_99_W12") (pintype "power_in"))
      (node (ref "U100") (pin "W13") (pinfunction "GND_100_W13") (pintype "power_in"))
      (node (ref "U100") (pin "W15") (pinfunction "GND_101_W15") (pintype "power_in"))
      (node (ref "U100") (pin "W16") (pinfunction "GND_102_W16") (pintype "power_in"))
      (node (ref "U100") (pin "W17") (pinfunction "GND_103_W17") (pintype "power_in"))
      (node (ref "U100") (pin "W18") (pinfunction "GND_104_W18") (pintype "power_in"))
      (node (ref "U100") (pin "W19") (pinfunction "GND_105_W19") (pintype "power_in"))
      (node (ref "U100") (pin "W3") (pinfunction "GND_93_W3") (pintype "power_in"))
      (node (ref "U100") (pin "W7") (pinfunction "GND_94_W7") (pintype "power_in"))
      (node (ref "U100") (pin "W8") (pinfunction "GND_95_W8") (pintype "power_in"))
      (node (ref "U100") (pin "W9") (pinfunction "GND_96_W9") (pintype "power_in"))
      (node (ref "U100") (pin "Y24") (pinfunction "GND_107_Y24") (pintype "power_in"))
      (node (ref "U100") (pin "Y5") (pinfunction "GND_106_Y5") (pintype "power_in"))
    )
    (net (code "5") (name "Net-(U100E-FA_ANA)") (class "Default")
      (node (ref "J11C") (pin "1") (pinfunction "1_1") (pintype "passive"))
      (node (ref "U100") (pin "A5") (pinfunction "FA_ANA_A5") (pintype "power_in"))
    )
    (net (code "6") (name "Net-(U100E-GPANAIO)") (class "Default")
      (node (ref "J10C") (pin "1") (pinfunction "1_1") (pintype "passive"))
      (node (ref "U100") (pin "C8") (pinfunction "GPANAIO_C8") (pintype "power_in"))
    )
    (net (code "7") (name "Net-(U100E-VDDPU_CAP_1)") (class "Default")
      (node (ref "C53C") (pin "1") (pinfunction "1_1") (pintype "passive"))
      (node (ref "C54C") (pin "1") (pinfunction "1_1") (pintype "passive"))
      (node (ref "C55C") (pin "1") (pinfunction "1_1") (pintype "passive"))
      (node (ref "C56C") (pin "1") (pinfunction "1_1") (pintype "passive"))
      (node (ref "C57C") (pin "1") (pinfunction "1_1") (pintype "passive"))
      (node (ref "C58C") (pin "1") (pinfunction "1_1") (pintype "passive"))
      (node (ref "C59C") (pin "1") (pinfunction "1_1") (pintype "passive"))
      (node (ref "C60C") (pin "1") (pinfunction "1_1") (pintype "passive"))
      (node (ref "U100") (pin "H17") (pinfunction "VDDPU_CAP_1_H17") (pintype "power_in"))
      (node (ref "U100") (pin "J17") (pinfunction "VDDPU_CAP_2_J17") (pintype "power_in"))
      (node (ref "U100") (pin "K17") (pinfunction "VDDPU_CAP_3_K17") (pintype "power_in"))
      (node (ref "U100") (pin "L17") (pinfunction "VDDPU_CAP_4_L17") (pintype "power_in"))
      (node (ref "U100") (pin "M17") (pinfunction "VDDPU_CAP_5_M17") (pintype "power_in"))
      (node (ref "U100") (pin "N17") (pinfunction "VDDPU_CAP_6_N17") (pintype "power_in"))
      (node (ref "U100") (pin "P17") (pinfunction "VDDPU_CAP_7_P17") (pintype "power_in"))
    )
    (net (code "8") (name "Net-(U100E-VDD_FA)") (class "Default")
      (node (ref "J12C") (pin "1") (pinfunction "1_1") (pintype "passive"))
      (node (ref "U100") (pin "B5") (pinfunction "VDD_FA_B5") (pintype "power_in"))
    )
    (net (code "9") (name "P2.5V_VGEN5") (class "Default")
      (node (ref "C25C") (pin "1") (pinfunction "1_1") (pintype "passive"))
      (node (ref "C28C") (pin "1") (pinfunction "1_1") (pintype "passive"))
      (node (ref "C73C") (pin "1") (pinfunction "1_1") (pintype "passive"))
      (node (ref "C75C") (pin "1") (pinfunction "1_1") (pintype "passive"))
      (node (ref "C82C") (pin "1") (pinfunction "1_1") (pintype "passive"))
      (node (ref "U100") (pin "G18") (pinfunction "NVCC_RGMII_G18") (pintype "power_in"))
      (node (ref "U100") (pin "N7") (pinfunction "NVCC_CSI_N7") (pintype "power_in"))
      (node (ref "U100") (pin "R19") (pinfunction "NVCC_ENET_R19") (pintype "power_in"))
    )
    (net (code "10") (name "P3.0V_STBY") (class "Default")
      (node (ref "C71C") (pin "1") (pinfunction "1_1") (pintype "passive"))
      (node (ref "D10C") (pin "2") (pinfunction "K_2") (pintype "passive"))
      (node (ref "U100") (pin "G11") (pinfunction "VDD_SNVS_IN_G11") (pintype "power_in"))
    )
    (net (code "11") (name "P3.0V_VDDHIGH_SW2") (class "Default")
      (node (ref "C67C") (pin "1") (pinfunction "1_1") (pintype "passive"))
      (node (ref "C68C") (pin "1") (pinfunction "1_1") (pintype "passive"))
      (node (ref "D10C") (pin "1") (pinfunction "A_1") (pintype "passive"))
      (node (ref "U100") (pin "H9") (pinfunction "VDDHIGH_IN_1_H9") (pintype "power_in"))
      (node (ref "U100") (pin "J9") (pinfunction "VDDHIGH_IN_2_J9") (pintype "power_in"))
    )
    (net (code "12") (name "P3.3V_DELAYED") (class "Default")
      (node (ref "C72C") (pin "1") (pinfunction "1_1") (pintype "passive"))
      (node (ref "C76C") (pin "1") (pinfunction "1_1") (pintype "passive"))
      (node (ref "C77C") (pin "1") (pinfunction "1_1") (pintype "passive"))
      (node (ref "C78C") (pin "1") (pinfunction "1_1") (pintype "passive"))
      (node (ref "C79C") (pin "1") (pinfunction "1_1") (pintype "passive"))
      (node (ref "C84C") (pin "1") (pinfunction "1_1") (pintype "passive"))
      (node (ref "C85C") (pin "1") (pinfunction "1_1") (pintype "passive"))
      (node (ref "C86C") (pin "1") (pinfunction "1_1") (pintype "passive"))
      (node (ref "C87C") (pin "1") (pinfunction "1_1") (pintype "passive"))
      (node (ref "C88C") (pin "1") (pinfunction "1_1") (pintype "passive"))
      (node (ref "U100") (pin "G14") (pinfunction "NVCC_SD3_G14") (pintype "power_in"))
      (node (ref "U100") (pin "G15") (pinfunction "NVCC_NANDF_G15") (pintype "power_in"))
      (node (ref "U100") (pin "G16") (pinfunction "NVCC_SD1_G16") (pintype "power_in"))
      (node (ref "U100") (pin "G17") (pinfunction "NVCC_SD2_G17") (pintype "power_in"))
      (node (ref "U100") (pin "J7") (pinfunction "NVCC_JTAG_J7") (pintype "power_in"))
      (node (ref "U100") (pin "K19") (pinfunction "NVCC_EIM0_K19") (pintype "power_in"))
      (node (ref "U100") (pin "L19") (pinfunction "NVCC_EIM1_L19") (pintype "power_in"))
      (node (ref "U100") (pin "M19") (pinfunction "NVCC_EIM2_M19") (pintype "power_in"))
      (node (ref "U100") (pin "P19") (pinfunction "NVCC_LCD_P19") (pintype "power_in"))
      (node (ref "U100") (pin "P7") (pinfunction "NVCC_GPIO_P7") (pintype "power_in"))
    )
    (net (code "13") (name "VCC_1.2V_SW1AB") (class "Default")
      (node (ref "C13C") (pin "1") (pinfunction "1_1") (pintype "passive"))
      (node (ref "C14C") (pin "1") (pinfunction "1_1") (pintype "passive"))
      (node (ref "C15C") (pin "1") (pinfunction "1_1") (pintype "passive"))
      (node (ref "C16C") (pin "1") (pinfunction "1_1") (pintype "passive"))
      (node (ref "C17C") (pin "1") (pinfunction "1_1") (pintype "passive"))
      (node (ref "C18C") (pin "1") (pinfunction "1_1") (pintype "passive"))
      (node (ref "C30C") (pin "1") (pinfunction "1_1") (pintype "passive"))
      (node (ref "C31C") (pin "1") (pinfunction "1_1") (pintype "passive"))
      (node (ref "C32C") (pin "1") (pinfunction "1_1") (pintype "passive"))
      (node (ref "C33C") (pin "1") (pinfunction "1_1") (pintype "passive"))
      (node (ref "C34C") (pin "1") (pinfunction "1_1") (pintype "passive"))
      (node (ref "C89C") (pin "1") (pinfunction "1_1") (pintype "passive"))
      (node (ref "C90C") (pin "1") (pinfunction "1_1") (pintype "passive"))
      (node (ref "C91C") (pin "1") (pinfunction "1_1") (pintype "passive"))
      (node (ref "C92C") (pin "1") (pinfunction "1_1") (pintype "passive"))
      (node (ref "C93C") (pin "1") (pinfunction "1_1") (pintype "passive"))
      (node (ref "U100") (pin "H14") (pinfunction "VDDARM_IN_1_H14") (pintype "power_in"))
      (node (ref "U100") (pin "J14") (pinfunction "VDDARM_IN_2_J14") (pintype "power_in"))
      (node (ref "U100") (pin "K14") (pinfunction "VDDARM_IN_3_K14") (pintype "power_in"))
      (node (ref "U100") (pin "K9") (pinfunction "VDDARM23_IN_1_K9") (pintype "power_in"))
      (node (ref "U100") (pin "L14") (pinfunction "VDDARM_IN_4_L14") (pintype "power_in"))
      (node (ref "U100") (pin "L9") (pinfunction "VDDARM23_IN_2_L9") (pintype "power_in"))
      (node (ref "U100") (pin "M14") (pinfunction "VDDARM_IN_5_M14") (pintype "power_in"))
      (node (ref "U100") (pin "M9") (pinfunction "VDDARM23_IN_3_M9") (pintype "power_in"))
      (node (ref "U100") (pin "N14") (pinfunction "VDDARM_IN_6_N14") (pintype "power_in"))
      (node (ref "U100") (pin "N9") (pinfunction "VDDARM23_IN_4_N9") (pintype "power_in"))
      (node (ref "U100") (pin "P14") (pinfunction "VDDARM_IN_7_P14") (pintype "power_in"))
      (node (ref "U100") (pin "P9") (pinfunction "VDDARM23_IN_5_P9") (pintype "power_in"))
      (node (ref "U100") (pin "R14") (pinfunction "VDDARM_IN_8_R14") (pintype "power_in"))
      (node (ref "U100") (pin "R9") (pinfunction "VDDARM23_IN_6_R9") (pintype "power_in"))
      (node (ref "U100") (pin "T9") (pinfunction "VDDARM23_IN_7_T9") (pintype "power_in"))
      (node (ref "U100") (pin "U9") (pinfunction "VDDARM23_IN_8_U9") (pintype "power_in"))
    )
    (net (code "14") (name "VDDSOC_CAP") (class "Default")
      (node (ref "C35C") (pin "1") (pinfunction "1_1") (pintype "passive"))
      (node (ref "C36C") (pin "1") (pinfunction "1_1") (pintype "passive"))
      (node (ref "C37C") (pin "1") (pinfunction "1_1") (pintype "passive"))
      (node (ref "C38C") (pin "1") (pinfunction "1_1") (pintype "passive"))
      (node (ref "C39C") (pin "1") (pinfunction "1_1") (pintype "passive"))
      (node (ref "C40C") (pin "1") (pinfunction "1_1") (pintype "passive"))
      (node (ref "C41C") (pin "1") (pinfunction "1_1") (pintype "passive"))
      (node (ref "C42C") (pin "1") (pinfunction "1_1") (pintype "passive"))
      (node (ref "C61C") (pin "1") (pinfunction "1_1") (pintype "passive"))
      (node (ref "C62C") (pin "1") (pinfunction "1_1") (pintype "passive"))
      (node (ref "U100") (pin "N12") (pinfunction "VDD_CACHE_CAP_N12") (pintype "power_in"))
      (node (ref "U100") (pin "R10") (pinfunction "VDDSOC_CAP_1_R10") (pintype "power_in"))
      (node (ref "U100") (pin "T10") (pinfunction "VDDSOC_CAP_2_T10") (pintype "power_in"))
      (node (ref "U100") (pin "T13") (pinfunction "VDDSOC_CAP_3_T13") (pintype "power_in"))
      (node (ref "U100") (pin "T14") (pinfunction "VDDSOC_CAP_4_T14") (pintype "power_in"))
      (node (ref "U100") (pin "U10") (pinfunction "VDDSOC_CAP_5_U10") (pintype "power_in"))
      (node (ref "U100") (pin "U13") (pinfunction "VDDSOC_CAP_6_U13") (pintype "power_in"))
      (node (ref "U100") (pin "U14") (pinfunction "VDDSOC_CAP_7_U14") (pintype "power_in"))
    )
    (net (code "15") (name "VDD_HIGH_CAP") (class "Default")
      (node (ref "C63C") (pin "1") (pinfunction "1_1") (pintype "passive"))
      (node (ref "C64C") (pin "1") (pinfunction "1_1") (pintype "passive"))
      (node (ref "C65C") (pin "1") (pinfunction "1_1") (pintype "passive"))
      (node (ref "C66C") (pin "1") (pinfunction "1_1") (pintype "passive"))
      (node (ref "C74C") (pin "1") (pinfunction "1_1") (pintype "passive"))
      (node (ref "U100") (pin "H10") (pinfunction "VDDHIGH_CAP_1_H10") (pintype "power_in"))
      (node (ref "U100") (pin "J10") (pinfunction "VDDHIGH_CAP_2_J10") (pintype "power_in"))
      (node (ref "U100") (pin "K7") (pinfunction "NVCC_MIPI_K7") (pintype "power_in"))
    )
    (net (code "16") (name "VDD_SOC_IN_SW1C") (class "Default")
      (node (ref "C43C") (pin "1") (pinfunction "1_1") (pintype "passive"))
      (node (ref "C44C") (pin "1") (pinfunction "1_1") (pintype "passive"))
      (node (ref "C45C") (pin "1") (pinfunction "1_1") (pintype "passive"))
      (node (ref "C46C") (pin "1") (pinfunction "1_1") (pintype "passive"))
      (node (ref "C47C") (pin "1") (pinfunction "1_1") (pintype "passive"))
      (node (ref "C48C") (pin "1") (pinfunction "1_1") (pintype "passive"))
      (node (ref "C49C") (pin "1") (pinfunction "1_1") (pintype "passive"))
      (node (ref "C50C") (pin "1") (pinfunction "1_1") (pintype "passive"))
      (node (ref "C51C") (pin "1") (pinfunction "1_1") (pintype "passive"))
      (node (ref "C52C") (pin "1") (pinfunction "1_1") (pintype "passive"))
      (node (ref "U100") (pin "H16") (pinfunction "VDDSOC_IN_1_H16") (pintype "power_in"))
      (node (ref "U100") (pin "J16") (pinfunction "VDDSOC_IN_2_J16") (pintype "power_in"))
      (node (ref "U100") (pin "K16") (pinfunction "VDDSOC_IN_3_K16") (pintype "power_in"))
      (node (ref "U100") (pin "L16") (pinfunction "VDDSOC_IN_4_L16") (pintype "power_in"))
      (node (ref "U100") (pin "M16") (pinfunction "VDDSOC_IN_5_M16") (pintype "power_in"))
      (node (ref "U100") (pin "N16") (pinfunction "VDDSOC_IN_6_N16") (pintype "power_in"))
      (node (ref "U100") (pin "P16") (pinfunction "VDDSOC_IN_7_P16") (pintype "power_in"))
      (node (ref "U100") (pin "R16") (pinfunction "VDDSOC_IN_8_R16") (pintype "power_in"))
      (node (ref "U100") (pin "T16") (pinfunction "VDDSOC_IN_9_T16") (pintype "power_in"))
      (node (ref "U100") (pin "U16") (pinfunction "VDDSOC_IN_10_U16") (pintype "power_in"))
    )
  )
)
